# SCH_d_00_e_02.net
KiCad netlist of a schematic drawn in EasyEDA
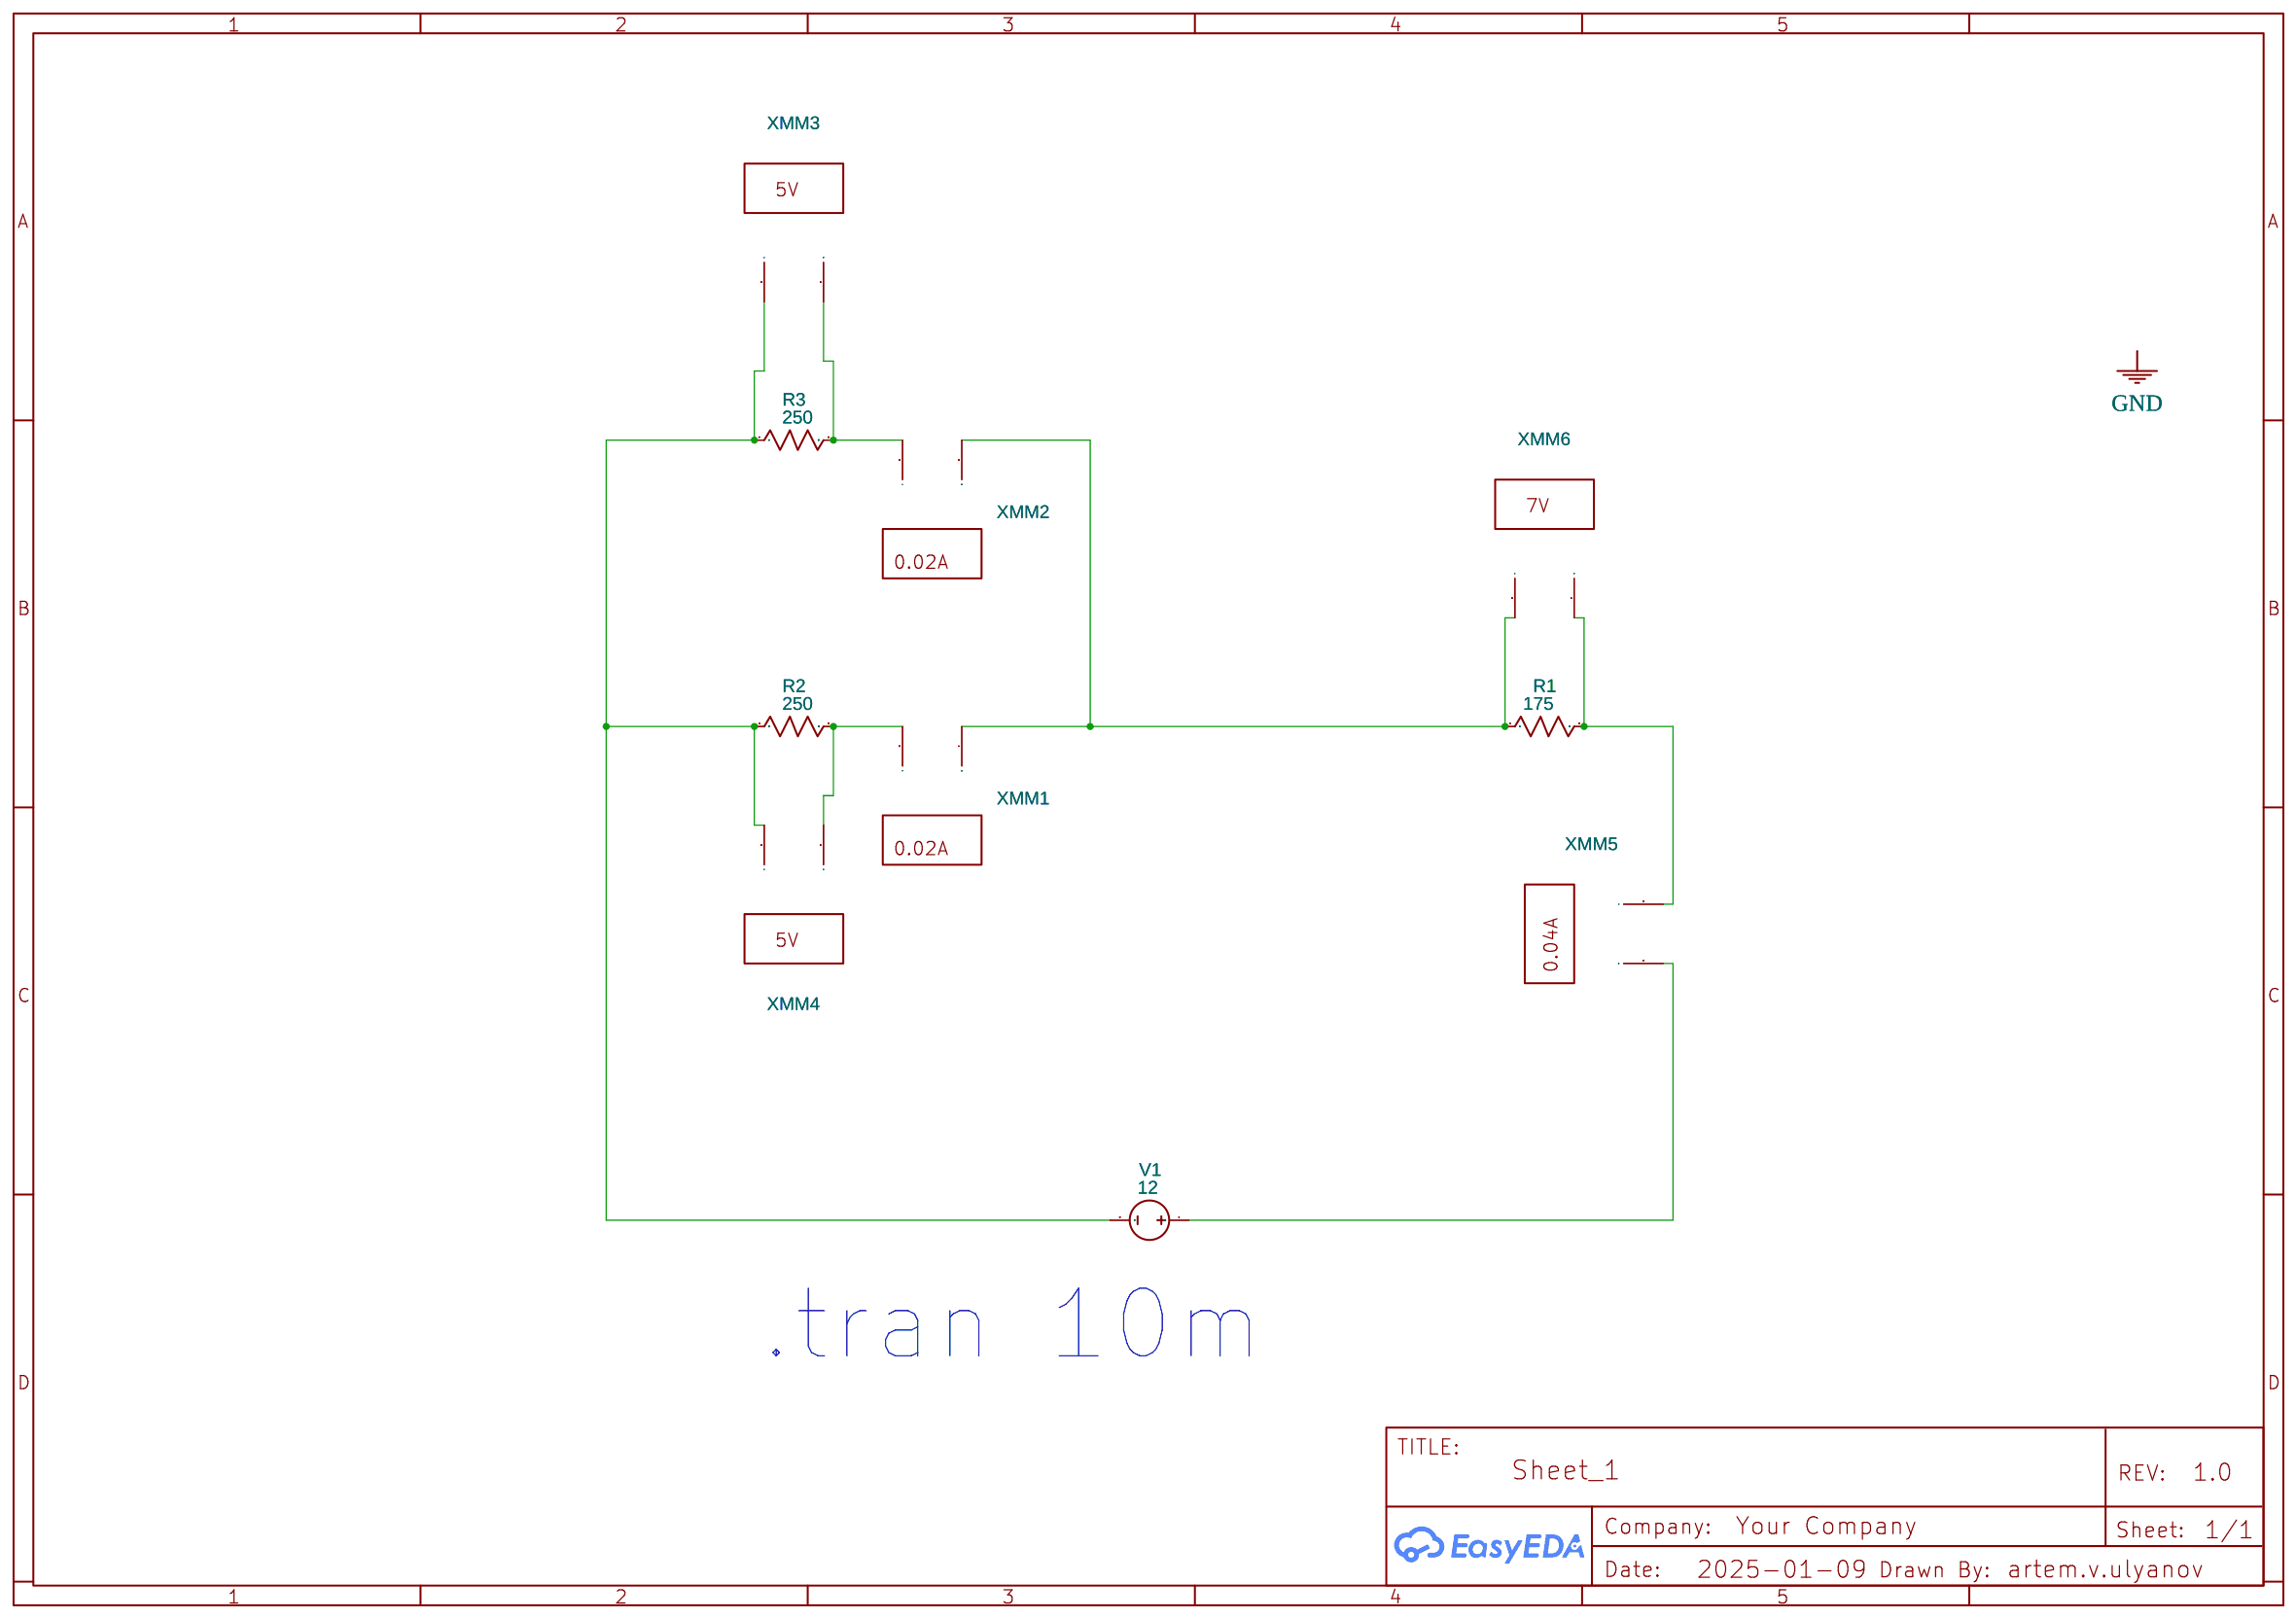
[diagram p0: schematic sheet]

(export (version "E")
  (design (tool "Eeschema 10.0.6"))
  (components
    (comp (ref "R1") (value "175") (libsource (lib "") (part "Resistor_US")))
    (comp (ref "R2") (value "250") (libsource (lib "") (part "Resistor_US")))
    (comp (ref "R3") (value "250") (libsource (lib "") (part "Resistor_US")))
    (comp (ref "V1") (value "12") (libsource (lib "") (part "VDC")))
    (comp (ref "XMM1") (value "Multimeter") (libsource (lib "") (part "MULTIMETER_1")))
    (comp (ref "XMM2") (value "Multimeter") (libsource (lib "") (part "MULTIMETER_1")))
    (comp (ref "XMM3") (value "Multimeter") (libsource (lib "") (part "MULTIMETER_2")))
    (comp (ref "XMM4") (value "Multimeter") (libsource (lib "") (part "MULTIMETER")))
    (comp (ref "XMM5") (value "Multimeter") (libsource (lib "") (part "MULTIMETER_4")))
    (comp (ref "XMM6") (value "Multimeter") (libsource (lib "") (part "MULTIMETER_3")))
  )
  (nets
    (net (code "2") (name "Net-(XMM1-+)") (class "Default")
      (node (ref "R1") (pin "1") (pinfunction "1_1") (pintype "unspecified"))
      (node (ref "XMM1") (pin "1") (pinfunction "+_1") (pintype "unspecified"))
      (node (ref "XMM2") (pin "1") (pinfunction "+_1") (pintype "unspecified"))
      (node (ref "XMM6") (pin "2") (pinfunction "I_2") (pintype "unspecified"))
    )
    (net (code "3") (name "Net-(XMM1-I)") (class "Default")
      (node (ref "R2") (pin "2") (pinfunction "2_2") (pintype "unspecified"))
      (node (ref "XMM1") (pin "2") (pinfunction "I_2") (pintype "unspecified"))
      (node (ref "XMM4") (pin "1") (pinfunction "+_1") (pintype "unspecified"))
    )
    (net (code "4") (name "Net-(XMM2-I)") (class "Default")
      (node (ref "R3") (pin "2") (pinfunction "2_2") (pintype "unspecified"))
      (node (ref "XMM2") (pin "2") (pinfunction "I_2") (pintype "unspecified"))
      (node (ref "XMM3") (pin "1") (pinfunction "+_1") (pintype "unspecified"))
    )
    (net (code "5") (name "Net-(XMM3-I)") (class "Default")
      (node (ref "R2") (pin "1") (pinfunction "1_1") (pintype "unspecified"))
      (node (ref "R3") (pin "1") (pinfunction "1_1") (pintype "unspecified"))
      (node (ref "V1") (pin "2") (pinfunction "2_2") (pintype "unspecified"))
      (node (ref "XMM3") (pin "2") (pinfunction "I_2") (pintype "unspecified"))
      (node (ref "XMM4") (pin "2") (pinfunction "I_2") (pintype "unspecified"))
    )
    (net (code "6") (name "Net-(XMM5-+)") (class "Default")
      (node (ref "V1") (pin "1") (pinfunction "1_1") (pintype "unspecified"))
      (node (ref "XMM5") (pin "1") (pinfunction "+_1") (pintype "unspecified"))
    )
    (net (code "7") (name "Net-(XMM5-I)") (class "Default")
      (node (ref "R1") (pin "2") (pinfunction "2_2") (pintype "unspecified"))
      (node (ref "XMM5") (pin "2") (pinfunction "I_2") (pintype "unspecified"))
      (node (ref "XMM6") (pin "1") (pinfunction "+_1") (pintype "unspecified"))
    )
  )
)
